# interfaces.net
KiCad netlist of a schematic drawn in Altium Designer
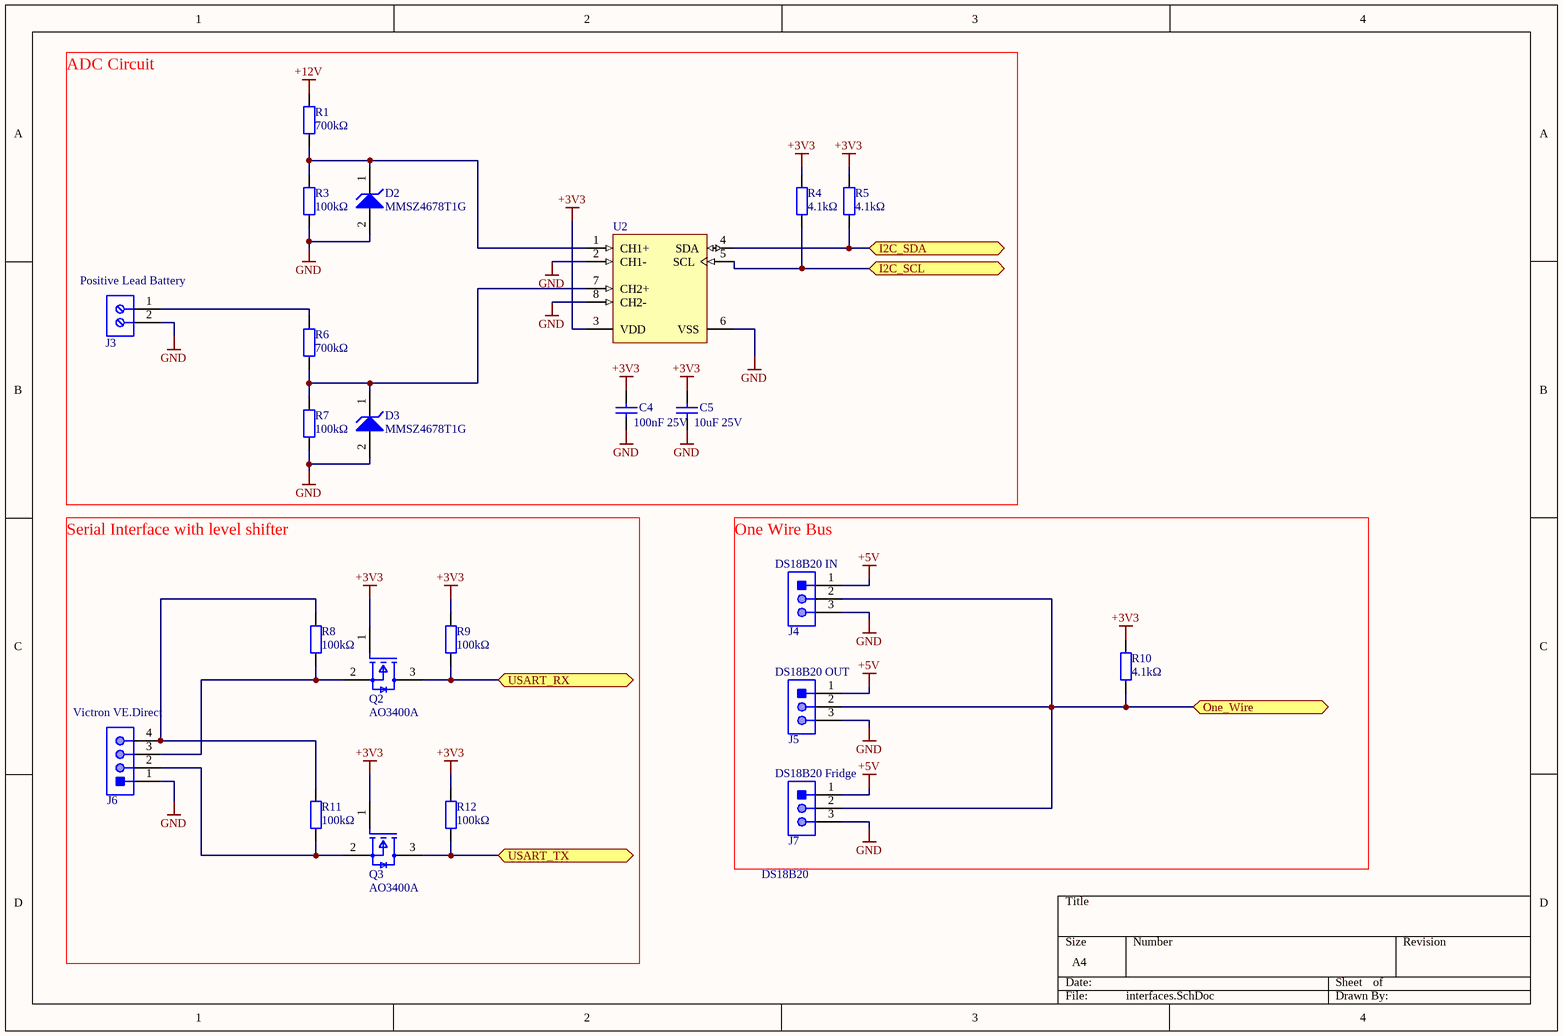
[diagram p0: interfaces.SchDoc]

(export (version "E")
  (design (tool "Eeschema 10.0.6"))
  (components
    (comp (ref "C4")
      (value "100nF 25V")
      (footprint "CAPC2013X88X50ML20T25")
      (description "Capacitor")
      (libsource (lib "Schlib") (part "Cap_0805"))
    )
    (comp (ref "C5")
      (value "10uF 25V")
      (footprint "CAPC2013X88X50ML20T25")
      (description "Capacitor")
      (libsource (lib "Schlib") (part "Cap_0805"))
    )
    (comp (ref "D2")
      (value "MMSZ4678T1G")
      (footprint "ONSC-SOD-123-2-425-04_V")
      (description "Zener Voltage Regulator, 500 mW, 2-Pin SOD-123, Pb-Free, Tape and Reel")
      (fields (field (name "MANUFACTURER") "On Semiconductor"))
      (libsource (lib "Altium Content Vault") (part "ONSC-K1A2-2"))
    )
    (comp (ref "D3")
      (value "MMSZ4678T1G")
      (footprint "ONSC-SOD-123-2-425-04_V")
      (description "Zener Voltage Regulator, 500 mW, 2-Pin SOD-123, Pb-Free, Tape and Reel")
      (fields (field (name "MANUFACTURER") "On Semiconductor"))
      (libsource (lib "Altium Content Vault") (part "ONSC-K1A2-2"))
    )
    (comp (ref "J3")
      (value "282836-2")
      (footprint "TECO-282836-2_V")
      (description "Female Header, Pitch 5 mm, 1 x 2 Position, Height 10 mm, Tail Length 3.5 mm, Rohs, Bulk")
      (fields (field (name "VOLTAGE") "300V") (field (name "MANUFACTURER") "TE Connectivity"))
      (libsource (lib "Altium Content Vault") (part "CN-1P-F-TB2"))
    )
    (comp (ref "J4")
      (value "JST-S3B-PH-SM4-TB-3_V")
      (footprint "JST-S3B-PH-SM4-TB-3_V")
      (libsource (lib "integrated_library") (part "CONNECTOR_JST-S3B-PH-SM4"))
    )
    (comp (ref "J5")
      (value "JST-S3B-PH-SM4-TB-3_V")
      (footprint "JST-S3B-PH-SM4-TB-3_V")
      (libsource (lib "integrated_library") (part "CONNECTOR_JST-S3B-PH-SM4"))
    )
    (comp (ref "J6")
      (value "JST-S4B-PH-SM4-TB-3_V")
      (footprint "JST-S4B-PH-SM4-TB-3_V")
      (libsource (lib "integrated_library") (part "CONNECTOR_JST-S4B-PH-SM4"))
    )
    (comp (ref "J7")
      (value "JST-S3B-PH-SM4-TB-3_V")
      (footprint "JST-S3B-PH-SM4-TB-3_V")
      (libsource (lib "integrated_library") (part "CONNECTOR_JST-S3B-PH-SM4"))
    )
    (comp (ref "Q2")
      (value "AO3400A")
      (footprint "SOT-23")
      (description "MOSFET N-CH 30V 5.7A SOT23")
      (libsource (lib "integrated_library") (part "MOSFET_AO3400A"))
    )
    (comp (ref "Q3")
      (value "AO3400A")
      (footprint "SOT-23")
      (description "MOSFET N-CH 30V 5.7A SOT23")
      (libsource (lib "integrated_library") (part "MOSFET_AO3400A"))
    )
    (comp (ref "R1")
      (value "700kΩ")
      (footprint "RESC2013X50X30ML20T20")
      (description "Resistor")
      (libsource (lib "PCB_Project") (part "Res_0805"))
    )
    (comp (ref "R3")
      (value "100kΩ")
      (footprint "RESC2013X50X30ML20T20")
      (description "Resistor")
      (libsource (lib "") (part "Res_0805_1"))
    )
    (comp (ref "R4")
      (value "4.1kΩ")
      (footprint "RESC2013X50X30ML20T20")
      (description "Resistor")
      (libsource (lib "") (part "Res_0805_1"))
    )
    (comp (ref "R5")
      (value "4.1kΩ")
      (footprint "RESC2013X50X30ML20T20")
      (description "Resistor")
      (libsource (lib "") (part "Res_0805_1"))
    )
    (comp (ref "R6")
      (value "700kΩ")
      (footprint "RESC2013X50X30ML20T20")
      (description "Resistor")
      (libsource (lib "PCB_Project") (part "Res_0805"))
    )
    (comp (ref "R7")
      (value "100kΩ")
      (footprint "RESC2013X50X30ML20T20")
      (description "Resistor")
      (libsource (lib "") (part "Res_0805_1"))
    )
    (comp (ref "R8")
      (value "100kΩ")
      (footprint "RESC2013X50X30ML20T20")
      (description "Resistor")
      (libsource (lib "PCB_Project") (part "Res_0805"))
    )
    (comp (ref "R9")
      (value "100kΩ")
      (footprint "RESC2013X50X30ML20T20")
      (description "Resistor")
      (libsource (lib "PCB_Project") (part "Res_0805"))
    )
    (comp (ref "R10")
      (value "4.1kΩ")
      (footprint "RESC2013X50X30ML20T20")
      (description "Resistor")
      (libsource (lib "") (part "Res_0805_1"))
    )
    (comp (ref "R11")
      (value "100kΩ")
      (footprint "RESC2013X50X30ML20T20")
      (description "Resistor")
      (libsource (lib "PCB_Project") (part "Res_0805"))
    )
    (comp (ref "R12")
      (value "100kΩ")
      (footprint "RESC2013X50X30ML20T20")
      (description "Resistor")
      (libsource (lib "PCB_Project") (part "Res_0805"))
    )
    (comp (ref "U2")
      (value "~")
      (footprint "SOIC-SN8_L")
      (libsource (lib "Altium Content Vault") (part "CON-ADC-MCP3426-8"))
    )
  )
  (nets
    (net (code "1") (name "+3V3") (class "Default")
      (node (ref "C4") (pin "2") (pinfunction "2_2") (pintype "passive"))
      (node (ref "C5") (pin "2") (pinfunction "2_2") (pintype "passive"))
      (node (ref "Q2") (pin "1") (pinfunction "G_1") (pintype "passive"))
      (node (ref "Q3") (pin "1") (pinfunction "G_1") (pintype "passive"))
      (node (ref "R10") (pin "2") (pinfunction "2_2") (pintype "passive"))
      (node (ref "R12") (pin "1") (pinfunction "1_1") (pintype "passive"))
      (node (ref "R4") (pin "2") (pinfunction "2_2") (pintype "passive"))
      (node (ref "R5") (pin "2") (pinfunction "2_2") (pintype "passive"))
      (node (ref "R9") (pin "1") (pinfunction "1_1") (pintype "passive"))
      (node (ref "U2") (pin "3") (pinfunction "VDD_3") (pintype "power_in"))
    )
    (net (code "2") (name "+5V") (class "Default")
      (node (ref "J4") (pin "1") (pinfunction "1_1") (pintype "passive"))
      (node (ref "J5") (pin "1") (pinfunction "1_1") (pintype "passive"))
      (node (ref "J7") (pin "1") (pinfunction "1_1") (pintype "passive"))
    )
    (net (code "3") (name "+12V") (class "Default")
      (node (ref "R1") (pin "1") (pinfunction "1_1") (pintype "passive"))
    )
    (net (code "4") (name "/I2C_SCL") (class "Default")
      (node (ref "R4") (pin "1") (pinfunction "1_1") (pintype "passive"))
      (node (ref "U2") (pin "5") (pinfunction "SCL_5") (pintype "input"))
    )
    (net (code "5") (name "/I2C_SDA") (class "Default")
      (node (ref "R5") (pin "1") (pinfunction "1_1") (pintype "passive"))
      (node (ref "U2") (pin "4") (pinfunction "SDA_4") (pintype "bidirectional"))
    )
    (net (code "6") (name "/One_Wire") (class "Default")
      (node (ref "J4") (pin "2") (pinfunction "2_2") (pintype "passive"))
      (node (ref "J5") (pin "2") (pinfunction "2_2") (pintype "passive"))
      (node (ref "J7") (pin "2") (pinfunction "2_2") (pintype "passive"))
      (node (ref "R10") (pin "1") (pinfunction "1_1") (pintype "passive"))
    )
    (net (code "7") (name "/USART_RX") (class "Default")
      (node (ref "Q2") (pin "3") (pinfunction "D_3") (pintype "passive"))
      (node (ref "R9") (pin "2") (pinfunction "2_2") (pintype "passive"))
    )
    (net (code "8") (name "/USART_TX") (class "Default")
      (node (ref "Q3") (pin "3") (pinfunction "D_3") (pintype "passive"))
      (node (ref "R12") (pin "2") (pinfunction "2_2") (pintype "passive"))
    )
    (net (code "9") (name "GND") (class "Default")
      (node (ref "C4") (pin "1") (pinfunction "1_1") (pintype "passive"))
      (node (ref "C5") (pin "1") (pinfunction "1_1") (pintype "passive"))
      (node (ref "D2") (pin "2") (pinfunction "A_2") (pintype "passive"))
      (node (ref "D3") (pin "2") (pinfunction "A_2") (pintype "passive"))
      (node (ref "J3") (pin "2") (pinfunction "2_2") (pintype "passive"))
      (node (ref "J4") (pin "3") (pinfunction "3_3") (pintype "passive"))
      (node (ref "J5") (pin "3") (pinfunction "3_3") (pintype "passive"))
      (node (ref "J6") (pin "1") (pinfunction "1_1") (pintype "passive"))
      (node (ref "J7") (pin "3") (pinfunction "3_3") (pintype "passive"))
      (node (ref "R3") (pin "1") (pinfunction "1_1") (pintype "passive"))
      (node (ref "R7") (pin "1") (pinfunction "1_1") (pintype "passive"))
      (node (ref "U2") (pin "2") (pinfunction "CH1-_2") (pintype "input"))
      (node (ref "U2") (pin "6") (pinfunction "VSS_6") (pintype "power_in"))
      (node (ref "U2") (pin "8") (pinfunction "CH2-_8") (pintype "input"))
    )
    (net (code "10") (name "Net-(D2-K)") (class "Default")
      (node (ref "D2") (pin "1") (pinfunction "K_1") (pintype "passive"))
      (node (ref "R1") (pin "2") (pinfunction "2_2") (pintype "passive"))
      (node (ref "R3") (pin "2") (pinfunction "2_2") (pintype "passive"))
      (node (ref "U2") (pin "1") (pinfunction "CH1+_1") (pintype "input"))
    )
    (net (code "11") (name "Net-(D3-K)") (class "Default")
      (node (ref "D3") (pin "1") (pinfunction "K_1") (pintype "passive"))
      (node (ref "R6") (pin "2") (pinfunction "2_2") (pintype "passive"))
      (node (ref "R7") (pin "2") (pinfunction "2_2") (pintype "passive"))
      (node (ref "U2") (pin "7") (pinfunction "CH2+_7") (pintype "input"))
    )
    (net (code "12") (name "Net-(J3-Pad1)") (class "Default")
      (node (ref "J3") (pin "1") (pinfunction "1_1") (pintype "passive"))
      (node (ref "R6") (pin "1") (pinfunction "1_1") (pintype "passive"))
    )
    (net (code "13") (name "Net-(J6-Pad4)") (class "Default")
      (node (ref "J6") (pin "4") (pinfunction "4_4") (pintype "passive"))
      (node (ref "R11") (pin "1") (pinfunction "1_1") (pintype "passive"))
      (node (ref "R8") (pin "1") (pinfunction "1_1") (pintype "passive"))
    )
    (net (code "14") (name "Net-(Q2-S)") (class "Default")
      (node (ref "J6") (pin "3") (pinfunction "3_3") (pintype "passive"))
      (node (ref "Q2") (pin "2") (pinfunction "S_2") (pintype "passive"))
      (node (ref "R8") (pin "2") (pinfunction "2_2") (pintype "passive"))
    )
    (net (code "15") (name "Net-(Q3-S)") (class "Default")
      (node (ref "J6") (pin "2") (pinfunction "2_2") (pintype "passive"))
      (node (ref "Q3") (pin "2") (pinfunction "S_2") (pintype "passive"))
      (node (ref "R11") (pin "2") (pinfunction "2_2") (pintype "passive"))
    )
  )
)
